# RS232_Adapter_ES_PCB.net
KiCad netlist of a schematic drawn in EAGLE
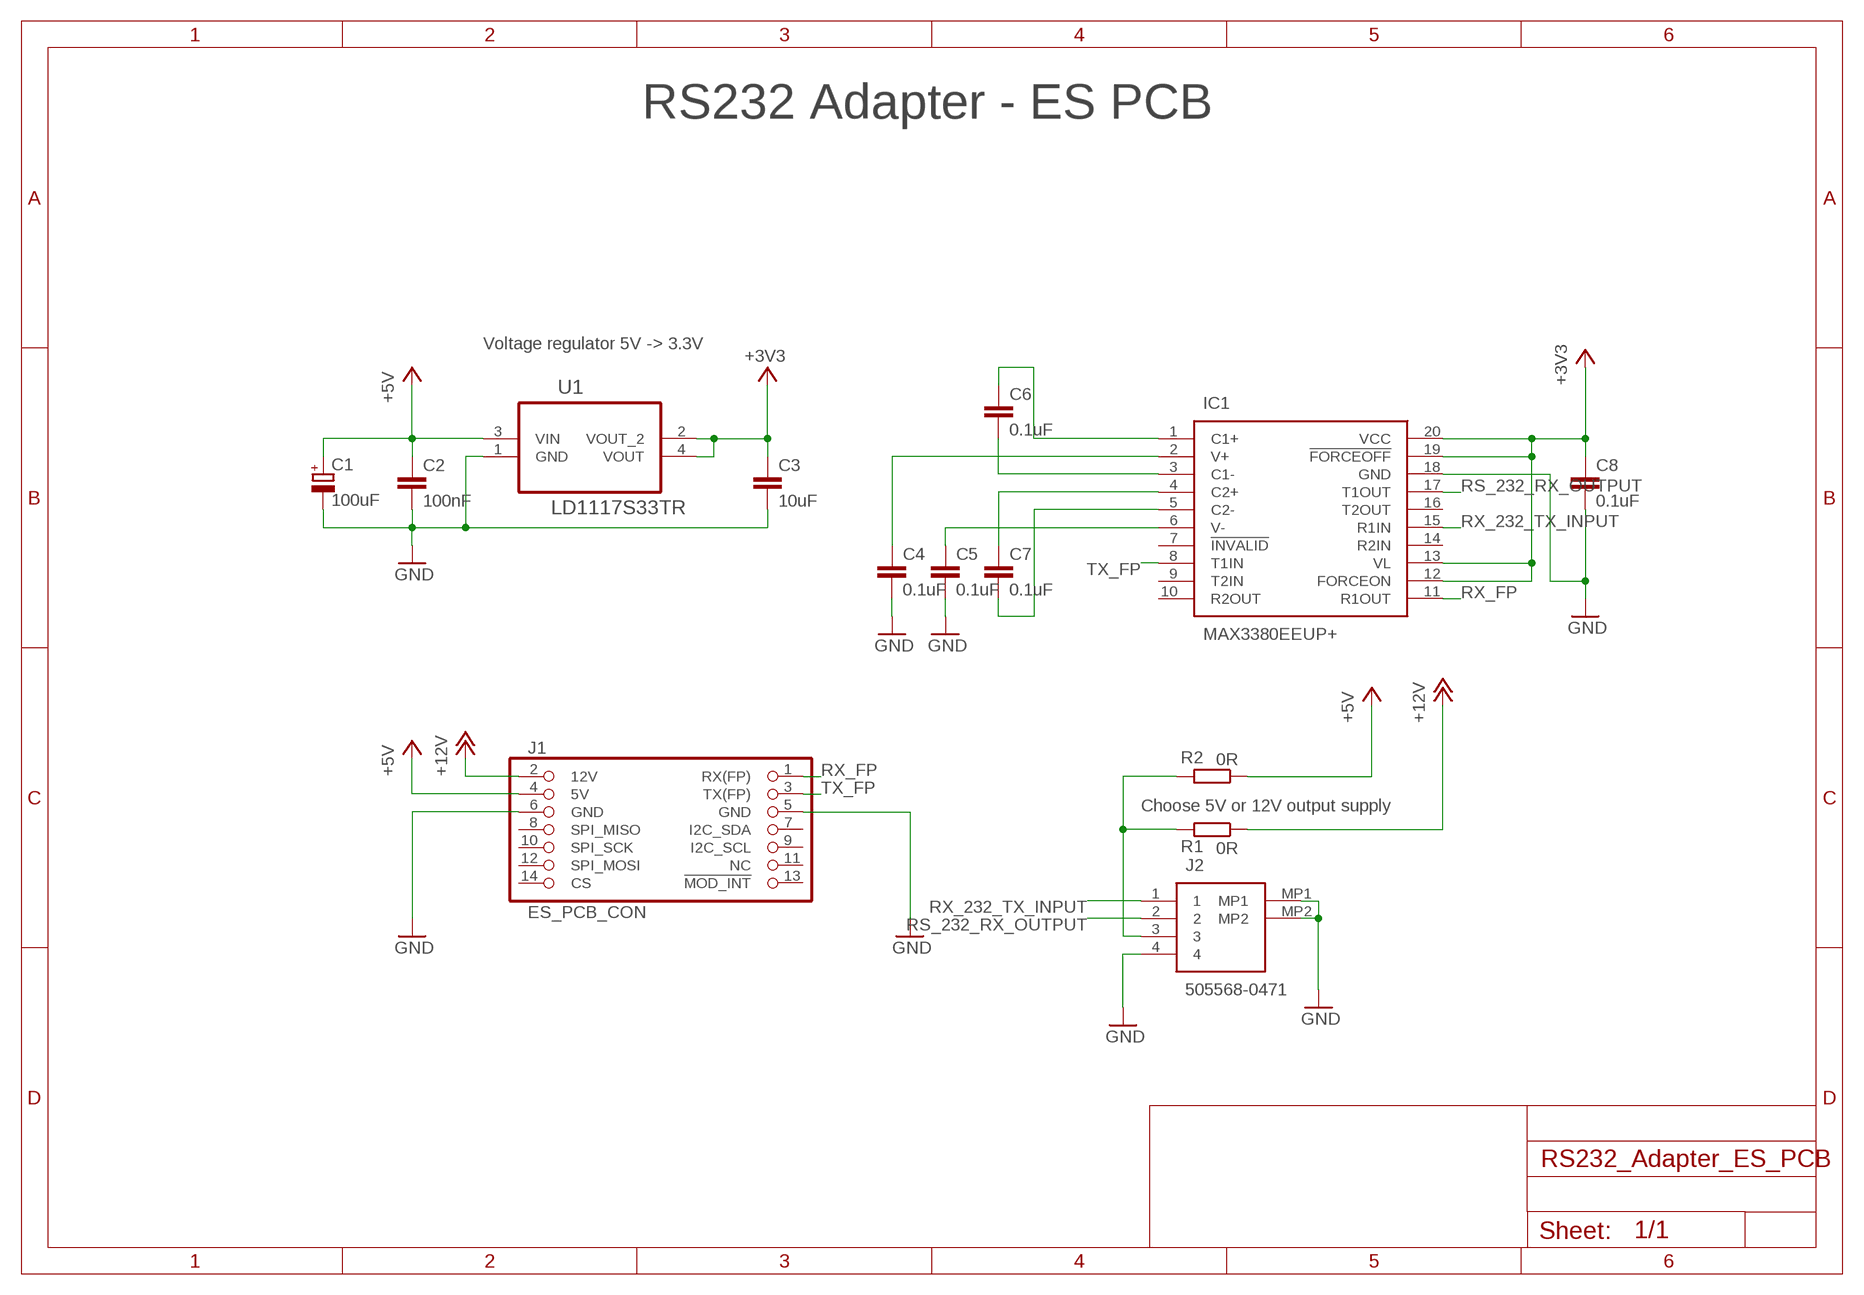
[diagram p0: schematic, sheet 1]

(export (version "E")
  (design (tool "Eeschema 10.0.6"))
  (components
    (comp (ref "C1")
      (value "100uF")
      (footprint "eagle-import:PANASONIC_C")
      (libsource (lib "eagle-import") (part "PANASONIC_C"))
    )
    (comp (ref "C2")
      (value "100nF")
      (footprint "eagle-import:C0603")
      (libsource (lib "eagle-import") (part "C0603"))
    )
    (comp (ref "C3")
      (value "10uF")
      (footprint "eagle-import:C0805")
      (libsource (lib "eagle-import") (part "C0805"))
    )
    (comp (ref "C4")
      (value "0.1uF")
      (footprint "eagle-import:C0603")
      (libsource (lib "eagle-import") (part "C0603"))
    )
    (comp (ref "C5")
      (value "0.1uF")
      (footprint "eagle-import:C0603")
      (libsource (lib "eagle-import") (part "C0603"))
    )
    (comp (ref "C6")
      (value "0.1uF")
      (footprint "eagle-import:C0603")
      (libsource (lib "eagle-import") (part "C0603"))
    )
    (comp (ref "C7")
      (value "0.1uF")
      (footprint "eagle-import:C0603")
      (libsource (lib "eagle-import") (part "C0603"))
    )
    (comp (ref "C8")
      (value "0.1uF")
      (footprint "eagle-import:C0603")
      (libsource (lib "eagle-import") (part "C0603"))
    )
    (comp (ref "IC1")
      (value "MAX3380EEUP+")
      (footprint "eagle-import:SOP65P640X110-20N")
      (fields (field (name "RS_PART_NUMBER") "7329452P"))
      (libsource (lib "eagle-import") (part "MAX3380EEUP+"))
    )
    (comp (ref "J1")
      (value "ES_PCB_CON")
      (footprint "eagle-import:ES_PCB_CON")
      (libsource (lib "eagle-import") (part "ES_PCB_CON"))
    )
    (comp (ref "J2")
      (value "505568-0471")
      (footprint "eagle-import:5055680471")
      (libsource (lib "eagle-import") (part "505568-0471"))
    )
    (comp (ref "R1")
      (value "0R")
      (footprint "eagle-import:R0603")
      (libsource (lib "eagle-import") (part "R0603"))
    )
    (comp (ref "R2")
      (value "0R")
      (footprint "eagle-import:R0603")
      (libsource (lib "eagle-import") (part "R0603"))
    )
    (comp (ref "U1")
      (value "LD1117S33TR")
      (footprint "eagle-import:SOT230P700X180-4N")
      (libsource (lib "eagle-import") (part "LD1117S33TR"))
    )
  )
  (nets
    (net (code "1") (name "+3V3") (class "Default")
      (node (ref "C3") (pin "1") (pinfunction "1_1") (pintype "passive"))
      (node (ref "C8") (pin "1") (pinfunction "1_1") (pintype "passive"))
      (node (ref "IC1") (pin "12") (pinfunction "FORCEON_12") (pintype "bidirectional"))
      (node (ref "IC1") (pin "13") (pinfunction "VL_13") (pintype "bidirectional"))
      (node (ref "IC1") (pin "19") (pinfunction "~{FORCEOFF}_19") (pintype "bidirectional"))
      (node (ref "IC1") (pin "20") (pinfunction "VCC_20") (pintype "bidirectional"))
      (node (ref "U1") (pin "2") (pinfunction "VOUT_2_2") (pintype "output"))
      (node (ref "U1") (pin "4") (pinfunction "VOUT_4") (pintype "output"))
    )
    (net (code "2") (name "+5V") (class "Default")
      (node (ref "C1") (pin "+") (pinfunction "+_+") (pintype "passive"))
      (node (ref "C2") (pin "1") (pinfunction "1_1") (pintype "passive"))
      (node (ref "J1") (pin "4") (pinfunction "5V_4") (pintype "passive"))
      (node (ref "R2") (pin "1") (pinfunction "1_1") (pintype "passive"))
      (node (ref "U1") (pin "3") (pinfunction "VIN_3") (pintype "input"))
    )
    (net (code "3") (name "+12V") (class "Default")
      (node (ref "J1") (pin "2") (pinfunction "12V_2") (pintype "passive"))
      (node (ref "R1") (pin "1") (pinfunction "1_1") (pintype "passive"))
    )
    (net (code "4") (name "/RS_232_RX_OUTPUT") (class "Default")
      (node (ref "IC1") (pin "17") (pinfunction "T1OUT_17") (pintype "bidirectional"))
      (node (ref "J2") (pin "2") (pinfunction "2_2") (pintype "bidirectional"))
    )
    (net (code "5") (name "/RX_232_TX_INPUT") (class "Default")
      (node (ref "IC1") (pin "15") (pinfunction "R1IN_15") (pintype "bidirectional"))
      (node (ref "J2") (pin "1") (pinfunction "1_1") (pintype "bidirectional"))
    )
    (net (code "6") (name "/RX_FP") (class "Default")
      (node (ref "IC1") (pin "11") (pinfunction "R1OUT_11") (pintype "bidirectional"))
      (node (ref "J1") (pin "1") (pinfunction "RX(FP)_1") (pintype "passive"))
    )
    (net (code "7") (name "/TX_FP") (class "Default")
      (node (ref "IC1") (pin "8") (pinfunction "T1IN_8") (pintype "bidirectional"))
      (node (ref "J1") (pin "3") (pinfunction "TX(FP)_3") (pintype "passive"))
    )
    (net (code "8") (name "GND") (class "Default")
      (node (ref "C1") (pin "-") (pinfunction "-_-") (pintype "passive"))
      (node (ref "C2") (pin "2") (pinfunction "2_2") (pintype "passive"))
      (node (ref "C3") (pin "2") (pinfunction "2_2") (pintype "passive"))
      (node (ref "C4") (pin "2") (pinfunction "2_2") (pintype "passive"))
      (node (ref "C5") (pin "2") (pinfunction "2_2") (pintype "passive"))
      (node (ref "C8") (pin "2") (pinfunction "2_2") (pintype "passive"))
      (node (ref "IC1") (pin "18") (pinfunction "GND_18") (pintype "bidirectional"))
      (node (ref "J1") (pin "5") (pinfunction "GND_5") (pintype "passive"))
      (node (ref "J1") (pin "6") (pinfunction "GND_6") (pintype "passive"))
      (node (ref "J2") (pin "4") (pinfunction "4_4") (pintype "bidirectional"))
      (node (ref "J2") (pin "MP1") (pinfunction "MP1_MP1") (pintype "bidirectional"))
      (node (ref "J2") (pin "MP2") (pinfunction "MP2_MP2") (pintype "bidirectional"))
      (node (ref "U1") (pin "1") (pinfunction "GND_1") (pintype "passive"))
    )
    (net (code "9") (name "Net-(IC1-C1+)") (class "Default")
      (node (ref "C6") (pin "1") (pinfunction "1_1") (pintype "passive"))
      (node (ref "IC1") (pin "1") (pinfunction "C1+_1") (pintype "bidirectional"))
    )
    (net (code "10") (name "Net-(IC1-C1-)") (class "Default")
      (node (ref "C6") (pin "2") (pinfunction "2_2") (pintype "passive"))
      (node (ref "IC1") (pin "3") (pinfunction "C1-_3") (pintype "bidirectional"))
    )
    (net (code "11") (name "Net-(IC1-C2+)") (class "Default")
      (node (ref "C7") (pin "1") (pinfunction "1_1") (pintype "passive"))
      (node (ref "IC1") (pin "4") (pinfunction "C2+_4") (pintype "bidirectional"))
    )
    (net (code "12") (name "Net-(IC1-C2-)") (class "Default")
      (node (ref "C7") (pin "2") (pinfunction "2_2") (pintype "passive"))
      (node (ref "IC1") (pin "5") (pinfunction "C2-_5") (pintype "bidirectional"))
    )
    (net (code "13") (name "Net-(IC1-V+)") (class "Default")
      (node (ref "C4") (pin "1") (pinfunction "1_1") (pintype "passive"))
      (node (ref "IC1") (pin "2") (pinfunction "V+_2") (pintype "bidirectional"))
    )
    (net (code "14") (name "Net-(IC1-V-)") (class "Default")
      (node (ref "C5") (pin "1") (pinfunction "1_1") (pintype "passive"))
      (node (ref "IC1") (pin "6") (pinfunction "V-_6") (pintype "bidirectional"))
    )
    (net (code "15") (name "Net-(J2-Pad3)") (class "Default")
      (node (ref "J2") (pin "3") (pinfunction "3_3") (pintype "bidirectional"))
      (node (ref "R1") (pin "2") (pinfunction "2_2") (pintype "passive"))
      (node (ref "R2") (pin "2") (pinfunction "2_2") (pintype "passive"))
    )
    (net (code "16") (name "unconnected-(IC1-R2IN-Pad14)") (class "Default")
      (node (ref "IC1") (pin "14") (pinfunction "R2IN_14") (pintype "bidirectional"))
    )
    (net (code "17") (name "unconnected-(IC1-R2OUT-Pad10)") (class "Default")
      (node (ref "IC1") (pin "10") (pinfunction "R2OUT_10") (pintype "bidirectional"))
    )
    (net (code "18") (name "unconnected-(IC1-T2IN-Pad9)") (class "Default")
      (node (ref "IC1") (pin "9") (pinfunction "T2IN_9") (pintype "bidirectional"))
    )
    (net (code "19") (name "unconnected-(IC1-T2OUT-Pad16)") (class "Default")
      (node (ref "IC1") (pin "16") (pinfunction "T2OUT_16") (pintype "bidirectional"))
    )
    (net (code "20") (name "unconnected-(IC1-~{INVALID}-Pad7)") (class "Default")
      (node (ref "IC1") (pin "7") (pinfunction "~{INVALID}_7") (pintype "bidirectional"))
    )
    (net (code "21") (name "unconnected-(J1-CS-Pad14)") (class "Default")
      (node (ref "J1") (pin "14") (pinfunction "CS_14") (pintype "passive"))
    )
    (net (code "22") (name "unconnected-(J1-I2C_SCL-Pad9)") (class "Default")
      (node (ref "J1") (pin "9") (pinfunction "I2C_SCL_9") (pintype "passive"))
    )
    (net (code "23") (name "unconnected-(J1-I2C_SDA-Pad7)") (class "Default")
      (node (ref "J1") (pin "7") (pinfunction "I2C_SDA_7") (pintype "passive"))
    )
    (net (code "24") (name "unconnected-(J1-NC-Pad11)") (class "Default")
      (node (ref "J1") (pin "11") (pinfunction "NC_11") (pintype "passive"))
    )
    (net (code "25") (name "unconnected-(J1-SPI_MISO-Pad8)") (class "Default")
      (node (ref "J1") (pin "8") (pinfunction "SPI_MISO_8") (pintype "passive"))
    )
    (net (code "26") (name "unconnected-(J1-SPI_MOSI-Pad12)") (class "Default")
      (node (ref "J1") (pin "12") (pinfunction "SPI_MOSI_12") (pintype "passive"))
    )
    (net (code "27") (name "unconnected-(J1-SPI_SCK-Pad10)") (class "Default")
      (node (ref "J1") (pin "10") (pinfunction "SPI_SCK_10") (pintype "passive"))
    )
    (net (code "28") (name "unconnected-(J1-~{MOD_INT}-Pad13)") (class "Default")
      (node (ref "J1") (pin "13") (pinfunction "~{MOD_INT}_13") (pintype "passive"))
    )
  )
)
